# pir_bigger_with_cap.net
KiCad netlist of a schematic drawn in EAGLE
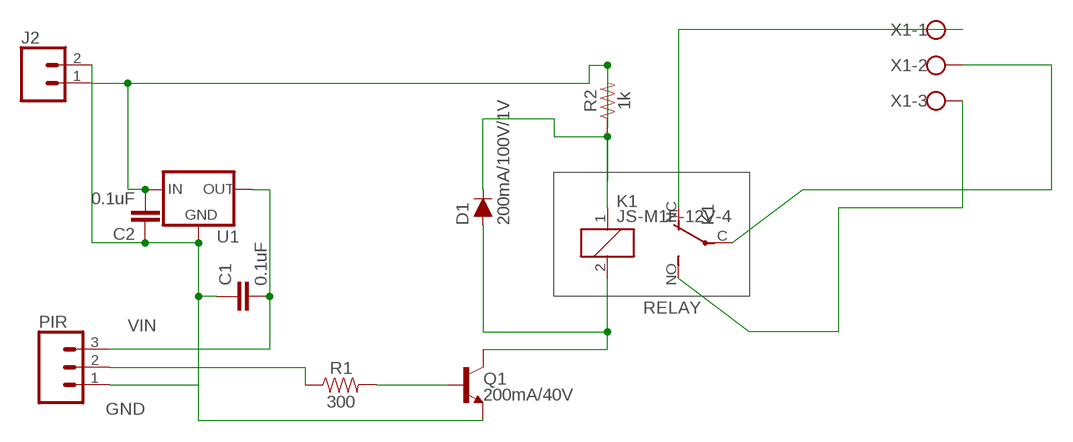
[diagram p0: schematic, sheet 1]

(export (version "E")
  (design (tool "Eeschema 10.0.6"))
  (components
    (comp (ref "C1")
      (value "0.1uF")
      (footprint "eagle-import:CAP-PTH-SMALL-KIT")
      (libsource (lib "eagle-import") (part "0.1UF-KIT-EZ-50V-20%"))
    )
    (comp (ref "C2")
      (value "0.1uF")
      (footprint "eagle-import:CAP-PTH-SMALL-KIT")
      (libsource (lib "eagle-import") (part "0.1UF-KIT-EZ-50V-20%"))
    )
    (comp (ref "D1")
      (value "200mA/100V/1V")
      (footprint "eagle-import:DIODE-1N4148")
      (libsource (lib "eagle-import") (part "DIODE-1N4148"))
    )
    (comp (ref "J2")
      (value "CONN_025MM")
      (footprint "eagle-import:SCREWTERMINAL-5MM-2")
      (libsource (lib "eagle-import") (part "CONN_025MM"))
    )
    (comp (ref "K1")
      (value "JS-M1F-12V-4")
      (footprint "eagle-import:JS-M")
      (libsource (lib "eagle-import") (part "JS-M1F-12V-4"))
    )
    (comp (ref "PIR")
      (value "CONN_03LONGPADS")
      (footprint "eagle-import:1X03_LONGPADS")
      (libsource (lib "eagle-import") (part "CONN_03LONGPADS"))
    )
    (comp (ref "Q1")
      (value "200mA/40V")
      (footprint "eagle-import:TO-92")
      (libsource (lib "eagle-import") (part "TRANS_NPN-2N3904"))
    )
    (comp (ref "R1")
      (value "300")
      (footprint "eagle-import:AXIAL-0.3")
      (libsource (lib "eagle-import") (part "10KOHM-HORIZ-1/4W-5%"))
    )
    (comp (ref "R2")
      (value "1k")
      (footprint "eagle-import:AXIAL-0.3")
      (libsource (lib "eagle-import") (part "10KOHM-HORIZ-1/4W-5%"))
    )
    (comp (ref "U1")
      (value "V_REG_78XXSINK")
      (footprint "eagle-import:TO220-IGO")
      (libsource (lib "eagle-import") (part "V_REG_78XXSINK"))
    )
    (comp (ref "X1")
      (value "W237-103")
      (footprint "eagle-import:W237-103")
      (fields (field (name "MPN") "237-103"))
      (libsource (lib "eagle-import") (part "W237-103"))
    )
  )
  (nets
    (net (code "1") (name "/GND") (class "Default")
      (node (ref "C1") (pin "1") (pinfunction "1_1") (pintype "passive"))
      (node (ref "C2") (pin "1") (pinfunction "1_1") (pintype "passive"))
      (node (ref "J2") (pin "2") (pinfunction "2_2") (pintype "passive"))
      (node (ref "PIR") (pin "1") (pinfunction "1_1") (pintype "passive"))
      (node (ref "Q1") (pin "1") (pinfunction "E_1") (pintype "passive"))
      (node (ref "U1") (pin "GND") (pinfunction "GND_GND") (pintype "input"))
    )
    (net (code "2") (name "/VIN") (class "Default")
      (node (ref "C1") (pin "2") (pinfunction "2_2") (pintype "passive"))
      (node (ref "PIR") (pin "3") (pinfunction "3_3") (pintype "passive"))
      (node (ref "U1") (pin "OUT") (pinfunction "OUT_OUT") (pintype "passive"))
    )
    (net (code "3") (name "Net-(K1B-O)") (class "Default")
      (node (ref "K1") (pin "NC") (pinfunction "O_NC") (pintype "passive"))
      (node (ref "X1") (pin "1") (pinfunction "KL_1") (pintype "passive"))
    )
    (net (code "4") (name "Net-(K1B-P)") (class "Default")
      (node (ref "K1") (pin "C") (pinfunction "P_C") (pintype "passive"))
      (node (ref "X1") (pin "2") (pinfunction "KL_2") (pintype "passive"))
    )
    (net (code "5") (name "Net-(K1B-S)") (class "Default")
      (node (ref "K1") (pin "NO") (pinfunction "S_NO") (pintype "passive"))
      (node (ref "X1") (pin "3") (pinfunction "KL_3") (pintype "passive"))
    )
    (net (code "6") (name "Net-(Q1-B)") (class "Default")
      (node (ref "Q1") (pin "2") (pinfunction "B_2") (pintype "passive"))
      (node (ref "R1") (pin "P$2") (pinfunction "2_P$2") (pintype "passive"))
    )
    (net (code "7") (name "Net-(Q1-C)") (class "Default")
      (node (ref "D1") (pin "A") (pinfunction "A_A") (pintype "passive"))
      (node (ref "K1") (pin "2") (pinfunction "2_2") (pintype "passive"))
      (node (ref "Q1") (pin "3") (pinfunction "C_3") (pintype "passive"))
    )
    (net (code "8") (name "Net-(R1-1)") (class "Default")
      (node (ref "PIR") (pin "2") (pinfunction "2_2") (pintype "passive"))
      (node (ref "R1") (pin "P$1") (pinfunction "1_P$1") (pintype "passive"))
    )
    (net (code "9") (name "Net-(R2-1)") (class "Default")
      (node (ref "D1") (pin "C") (pinfunction "C_C") (pintype "passive"))
      (node (ref "K1") (pin "1") (pinfunction "1_1") (pintype "passive"))
      (node (ref "R2") (pin "P$1") (pinfunction "1_P$1") (pintype "passive"))
    )
    (net (code "10") (name "Net-(R2-2)") (class "Default")
      (node (ref "C2") (pin "2") (pinfunction "2_2") (pintype "passive"))
      (node (ref "J2") (pin "1") (pinfunction "1_1") (pintype "passive"))
      (node (ref "R2") (pin "P$2") (pinfunction "2_P$2") (pintype "passive"))
      (node (ref "U1") (pin "IN") (pinfunction "IN_IN") (pintype "input"))
    )
  )
)
